# linefollower_L293D.net
KiCad netlist of a schematic drawn in EAGLE
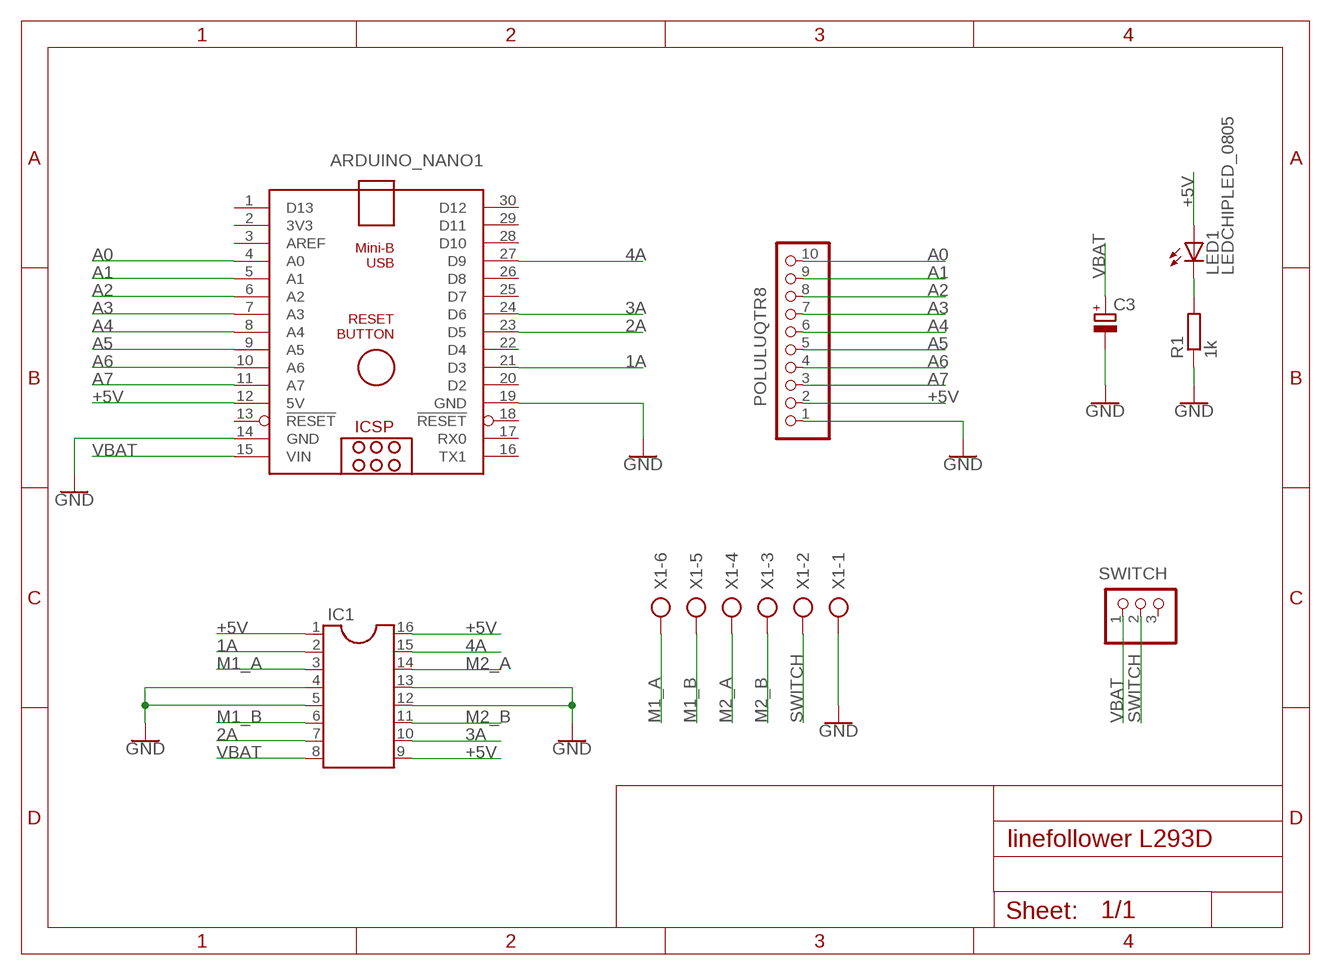
[diagram p0: schematic, sheet 1]

(export (version "E")
  (design (tool "Eeschema 10.0.6"))
  (components
    (comp (ref "ARDUINO_NANO1")
      (value "ARDUINO_NANO")
      (footprint "eagle-import:ARDUINO_NANO")
      (libsource (lib "eagle-import") (part "ARDUINO_NANO"))
    )
    (comp (ref "C3")
      (value "UCD1V221MNL1GS")
      (footprint "eagle-import:CAPAE830X1050")
      (libsource (lib "eagle-import") (part "UCD1V221MNL1GS"))
    )
    (comp (ref "IC1")
      (value "DIL16")
      (footprint "eagle-import:DIL16")
      (libsource (lib "eagle-import") (part "DIL16"))
    )
    (comp (ref "LED1")
      (value "LEDCHIPLED_0805")
      (footprint "eagle-import:CHIPLED_0805")
      (libsource (lib "eagle-import") (part "LEDCHIPLED_0805"))
    )
    (comp (ref "POLULUQTR8")
      (value "PINHD-1X10")
      (footprint "eagle-import:1X10")
      (libsource (lib "eagle-import") (part "PINHD-1X10"))
    )
    (comp (ref "R1")
      (value "1k")
      (footprint "eagle-import:R0805")
      (libsource (lib "eagle-import") (part "R-EU_R0805"))
    )
    (comp (ref "SWITCH")
      (value "PINHD-1X3")
      (footprint "eagle-import:1X03")
      (libsource (lib "eagle-import") (part "PINHD-1X3"))
    )
    (comp (ref "X1")
      (value "AK500/6")
      (footprint "eagle-import:AK500_6")
      (libsource (lib "eagle-import") (part "AK500/6"))
    )
  )
  (nets
    (net (code "1") (name "/+5V") (class "Default")
      (node (ref "ARDUINO_NANO1") (pin "12") (pinfunction "5V_12") (pintype "power_in"))
      (node (ref "IC1") (pin "1") (pinfunction "1_1") (pintype "passive"))
      (node (ref "IC1") (pin "16") (pinfunction "16_16") (pintype "passive"))
      (node (ref "IC1") (pin "9") (pinfunction "9_9") (pintype "passive"))
      (node (ref "LED1") (pin "A") (pinfunction "A_A") (pintype "passive"))
      (node (ref "POLULUQTR8") (pin "2") (pinfunction "2_2") (pintype "passive"))
    )
    (net (code "2") (name "/1A") (class "Default")
      (node (ref "ARDUINO_NANO1") (pin "21") (pinfunction "D3_21") (pintype "bidirectional"))
      (node (ref "IC1") (pin "2") (pinfunction "2_2") (pintype "passive"))
    )
    (net (code "3") (name "/2A") (class "Default")
      (node (ref "ARDUINO_NANO1") (pin "23") (pinfunction "D5_23") (pintype "bidirectional"))
      (node (ref "IC1") (pin "7") (pinfunction "7_7") (pintype "passive"))
    )
    (net (code "4") (name "/3A") (class "Default")
      (node (ref "ARDUINO_NANO1") (pin "24") (pinfunction "D6_24") (pintype "bidirectional"))
      (node (ref "IC1") (pin "10") (pinfunction "10_10") (pintype "passive"))
    )
    (net (code "5") (name "/4A") (class "Default")
      (node (ref "ARDUINO_NANO1") (pin "27") (pinfunction "D9_27") (pintype "bidirectional"))
      (node (ref "IC1") (pin "15") (pinfunction "15_15") (pintype "passive"))
    )
    (net (code "6") (name "/A0") (class "Default")
      (node (ref "ARDUINO_NANO1") (pin "4") (pinfunction "A0_4") (pintype "bidirectional"))
      (node (ref "POLULUQTR8") (pin "10") (pinfunction "10_10") (pintype "passive"))
    )
    (net (code "7") (name "/A1") (class "Default")
      (node (ref "ARDUINO_NANO1") (pin "5") (pinfunction "A1_5") (pintype "bidirectional"))
      (node (ref "POLULUQTR8") (pin "9") (pinfunction "9_9") (pintype "passive"))
    )
    (net (code "8") (name "/A2") (class "Default")
      (node (ref "ARDUINO_NANO1") (pin "6") (pinfunction "A2_6") (pintype "bidirectional"))
      (node (ref "POLULUQTR8") (pin "8") (pinfunction "8_8") (pintype "passive"))
    )
    (net (code "9") (name "/A3") (class "Default")
      (node (ref "ARDUINO_NANO1") (pin "7") (pinfunction "A3_7") (pintype "bidirectional"))
      (node (ref "POLULUQTR8") (pin "7") (pinfunction "7_7") (pintype "passive"))
    )
    (net (code "10") (name "/A4") (class "Default")
      (node (ref "ARDUINO_NANO1") (pin "8") (pinfunction "A4_8") (pintype "bidirectional"))
      (node (ref "POLULUQTR8") (pin "6") (pinfunction "6_6") (pintype "passive"))
    )
    (net (code "11") (name "/A5") (class "Default")
      (node (ref "ARDUINO_NANO1") (pin "9") (pinfunction "A5_9") (pintype "bidirectional"))
      (node (ref "POLULUQTR8") (pin "5") (pinfunction "5_5") (pintype "passive"))
    )
    (net (code "12") (name "/A6") (class "Default")
      (node (ref "ARDUINO_NANO1") (pin "10") (pinfunction "A6_10") (pintype "bidirectional"))
      (node (ref "POLULUQTR8") (pin "4") (pinfunction "4_4") (pintype "passive"))
    )
    (net (code "13") (name "/A7") (class "Default")
      (node (ref "ARDUINO_NANO1") (pin "11") (pinfunction "A7_11") (pintype "bidirectional"))
      (node (ref "POLULUQTR8") (pin "3") (pinfunction "3_3") (pintype "passive"))
    )
    (net (code "14") (name "/M1_A") (class "Default")
      (node (ref "IC1") (pin "3") (pinfunction "3_3") (pintype "passive"))
      (node (ref "X1") (pin "6") (pinfunction "KL_6") (pintype "passive"))
    )
    (net (code "15") (name "/M1_B") (class "Default")
      (node (ref "IC1") (pin "6") (pinfunction "6_6") (pintype "passive"))
      (node (ref "X1") (pin "5") (pinfunction "KL_5") (pintype "passive"))
    )
    (net (code "16") (name "/M2_A") (class "Default")
      (node (ref "IC1") (pin "14") (pinfunction "14_14") (pintype "passive"))
      (node (ref "X1") (pin "4") (pinfunction "KL_4") (pintype "passive"))
    )
    (net (code "17") (name "/M2_B") (class "Default")
      (node (ref "IC1") (pin "11") (pinfunction "11_11") (pintype "passive"))
      (node (ref "X1") (pin "3") (pinfunction "KL_3") (pintype "passive"))
    )
    (net (code "18") (name "/SWITCH") (class "Default")
      (node (ref "SWITCH") (pin "2") (pinfunction "2_2") (pintype "passive"))
      (node (ref "X1") (pin "2") (pinfunction "KL_2") (pintype "passive"))
    )
    (net (code "19") (name "/VBAT") (class "Default")
      (node (ref "ARDUINO_NANO1") (pin "15") (pinfunction "VIN_15") (pintype "power_in"))
      (node (ref "C3") (pin "1") (pinfunction "+_1") (pintype "passive"))
      (node (ref "IC1") (pin "8") (pinfunction "8_8") (pintype "passive"))
      (node (ref "SWITCH") (pin "1") (pinfunction "1_1") (pintype "passive"))
    )
    (net (code "20") (name "GND") (class "Default")
      (node (ref "ARDUINO_NANO1") (pin "14") (pinfunction "GND_14") (pintype "power_in"))
      (node (ref "ARDUINO_NANO1") (pin "19") (pinfunction "GND_19") (pintype "power_in"))
      (node (ref "C3") (pin "2") (pinfunction "-_2") (pintype "passive"))
      (node (ref "IC1") (pin "12") (pinfunction "12_12") (pintype "passive"))
      (node (ref "IC1") (pin "13") (pinfunction "13_13") (pintype "passive"))
      (node (ref "IC1") (pin "4") (pinfunction "4_4") (pintype "passive"))
      (node (ref "IC1") (pin "5") (pinfunction "5_5") (pintype "passive"))
      (node (ref "POLULUQTR8") (pin "1") (pinfunction "1_1") (pintype "passive"))
      (node (ref "R1") (pin "1") (pinfunction "1_1") (pintype "passive"))
      (node (ref "X1") (pin "1") (pinfunction "KL_1") (pintype "passive"))
    )
    (net (code "21") (name "Net-(LED1-PadC)") (class "Default")
      (node (ref "LED1") (pin "C") (pinfunction "C_C") (pintype "passive"))
      (node (ref "R1") (pin "2") (pinfunction "2_2") (pintype "passive"))
    )
    (net (code "22") (name "unconnected-(ARDUINO_NANO1-3V3-Pad2)") (class "Default")
      (node (ref "ARDUINO_NANO1") (pin "2") (pinfunction "3V3_2") (pintype "output"))
    )
    (net (code "23") (name "unconnected-(ARDUINO_NANO1-AREF-Pad3)") (class "Default")
      (node (ref "ARDUINO_NANO1") (pin "3") (pinfunction "AREF_3") (pintype "input"))
    )
    (net (code "24") (name "unconnected-(ARDUINO_NANO1-D2-Pad20)") (class "Default")
      (node (ref "ARDUINO_NANO1") (pin "20") (pinfunction "D2_20") (pintype "bidirectional"))
    )
    (net (code "25") (name "unconnected-(ARDUINO_NANO1-D4-Pad22)") (class "Default")
      (node (ref "ARDUINO_NANO1") (pin "22") (pinfunction "D4_22") (pintype "bidirectional"))
    )
    (net (code "26") (name "unconnected-(ARDUINO_NANO1-D7-Pad25)") (class "Default")
      (node (ref "ARDUINO_NANO1") (pin "25") (pinfunction "D7_25") (pintype "bidirectional"))
    )
    (net (code "27") (name "unconnected-(ARDUINO_NANO1-D8-Pad26)") (class "Default")
      (node (ref "ARDUINO_NANO1") (pin "26") (pinfunction "D8_26") (pintype "bidirectional"))
    )
    (net (code "28") (name "unconnected-(ARDUINO_NANO1-D10-Pad28)") (class "Default")
      (node (ref "ARDUINO_NANO1") (pin "28") (pinfunction "D10_28") (pintype "bidirectional"))
    )
    (net (code "29") (name "unconnected-(ARDUINO_NANO1-D11-Pad29)") (class "Default")
      (node (ref "ARDUINO_NANO1") (pin "29") (pinfunction "D11_29") (pintype "bidirectional"))
    )
    (net (code "30") (name "unconnected-(ARDUINO_NANO1-D12-Pad30)") (class "Default")
      (node (ref "ARDUINO_NANO1") (pin "30") (pinfunction "D12_30") (pintype "bidirectional"))
    )
    (net (code "31") (name "unconnected-(ARDUINO_NANO1-D13-Pad1)") (class "Default")
      (node (ref "ARDUINO_NANO1") (pin "1") (pinfunction "D13_1") (pintype "bidirectional"))
    )
    (net (code "32") (name "unconnected-(ARDUINO_NANO1-RX0-Pad17)") (class "Default")
      (node (ref "ARDUINO_NANO1") (pin "17") (pinfunction "RX0_17") (pintype "bidirectional"))
    )
    (net (code "33") (name "unconnected-(ARDUINO_NANO1-TX1-Pad16)") (class "Default")
      (node (ref "ARDUINO_NANO1") (pin "16") (pinfunction "TX1_16") (pintype "bidirectional"))
    )
    (net (code "34") (name "unconnected-(ARDUINO_NANO1-~{RESET}-Pad13)") (class "Default")
      (node (ref "ARDUINO_NANO1") (pin "13") (pinfunction "~{RESET}_13") (pintype "input"))
    )
    (net (code "35") (name "unconnected-(ARDUINO_NANO1-~{RESET}-Pad18)") (class "Default")
      (node (ref "ARDUINO_NANO1") (pin "18") (pinfunction "~{RESET}_18") (pintype "input"))
    )
    (net (code "36") (name "unconnected-(SWITCH-Pad3)") (class "Default")
      (node (ref "SWITCH") (pin "3") (pinfunction "3_3") (pintype "passive"))
    )
  )
)
